# mix1_LO1.net
KiCad netlist of a schematic drawn in Altium Designer
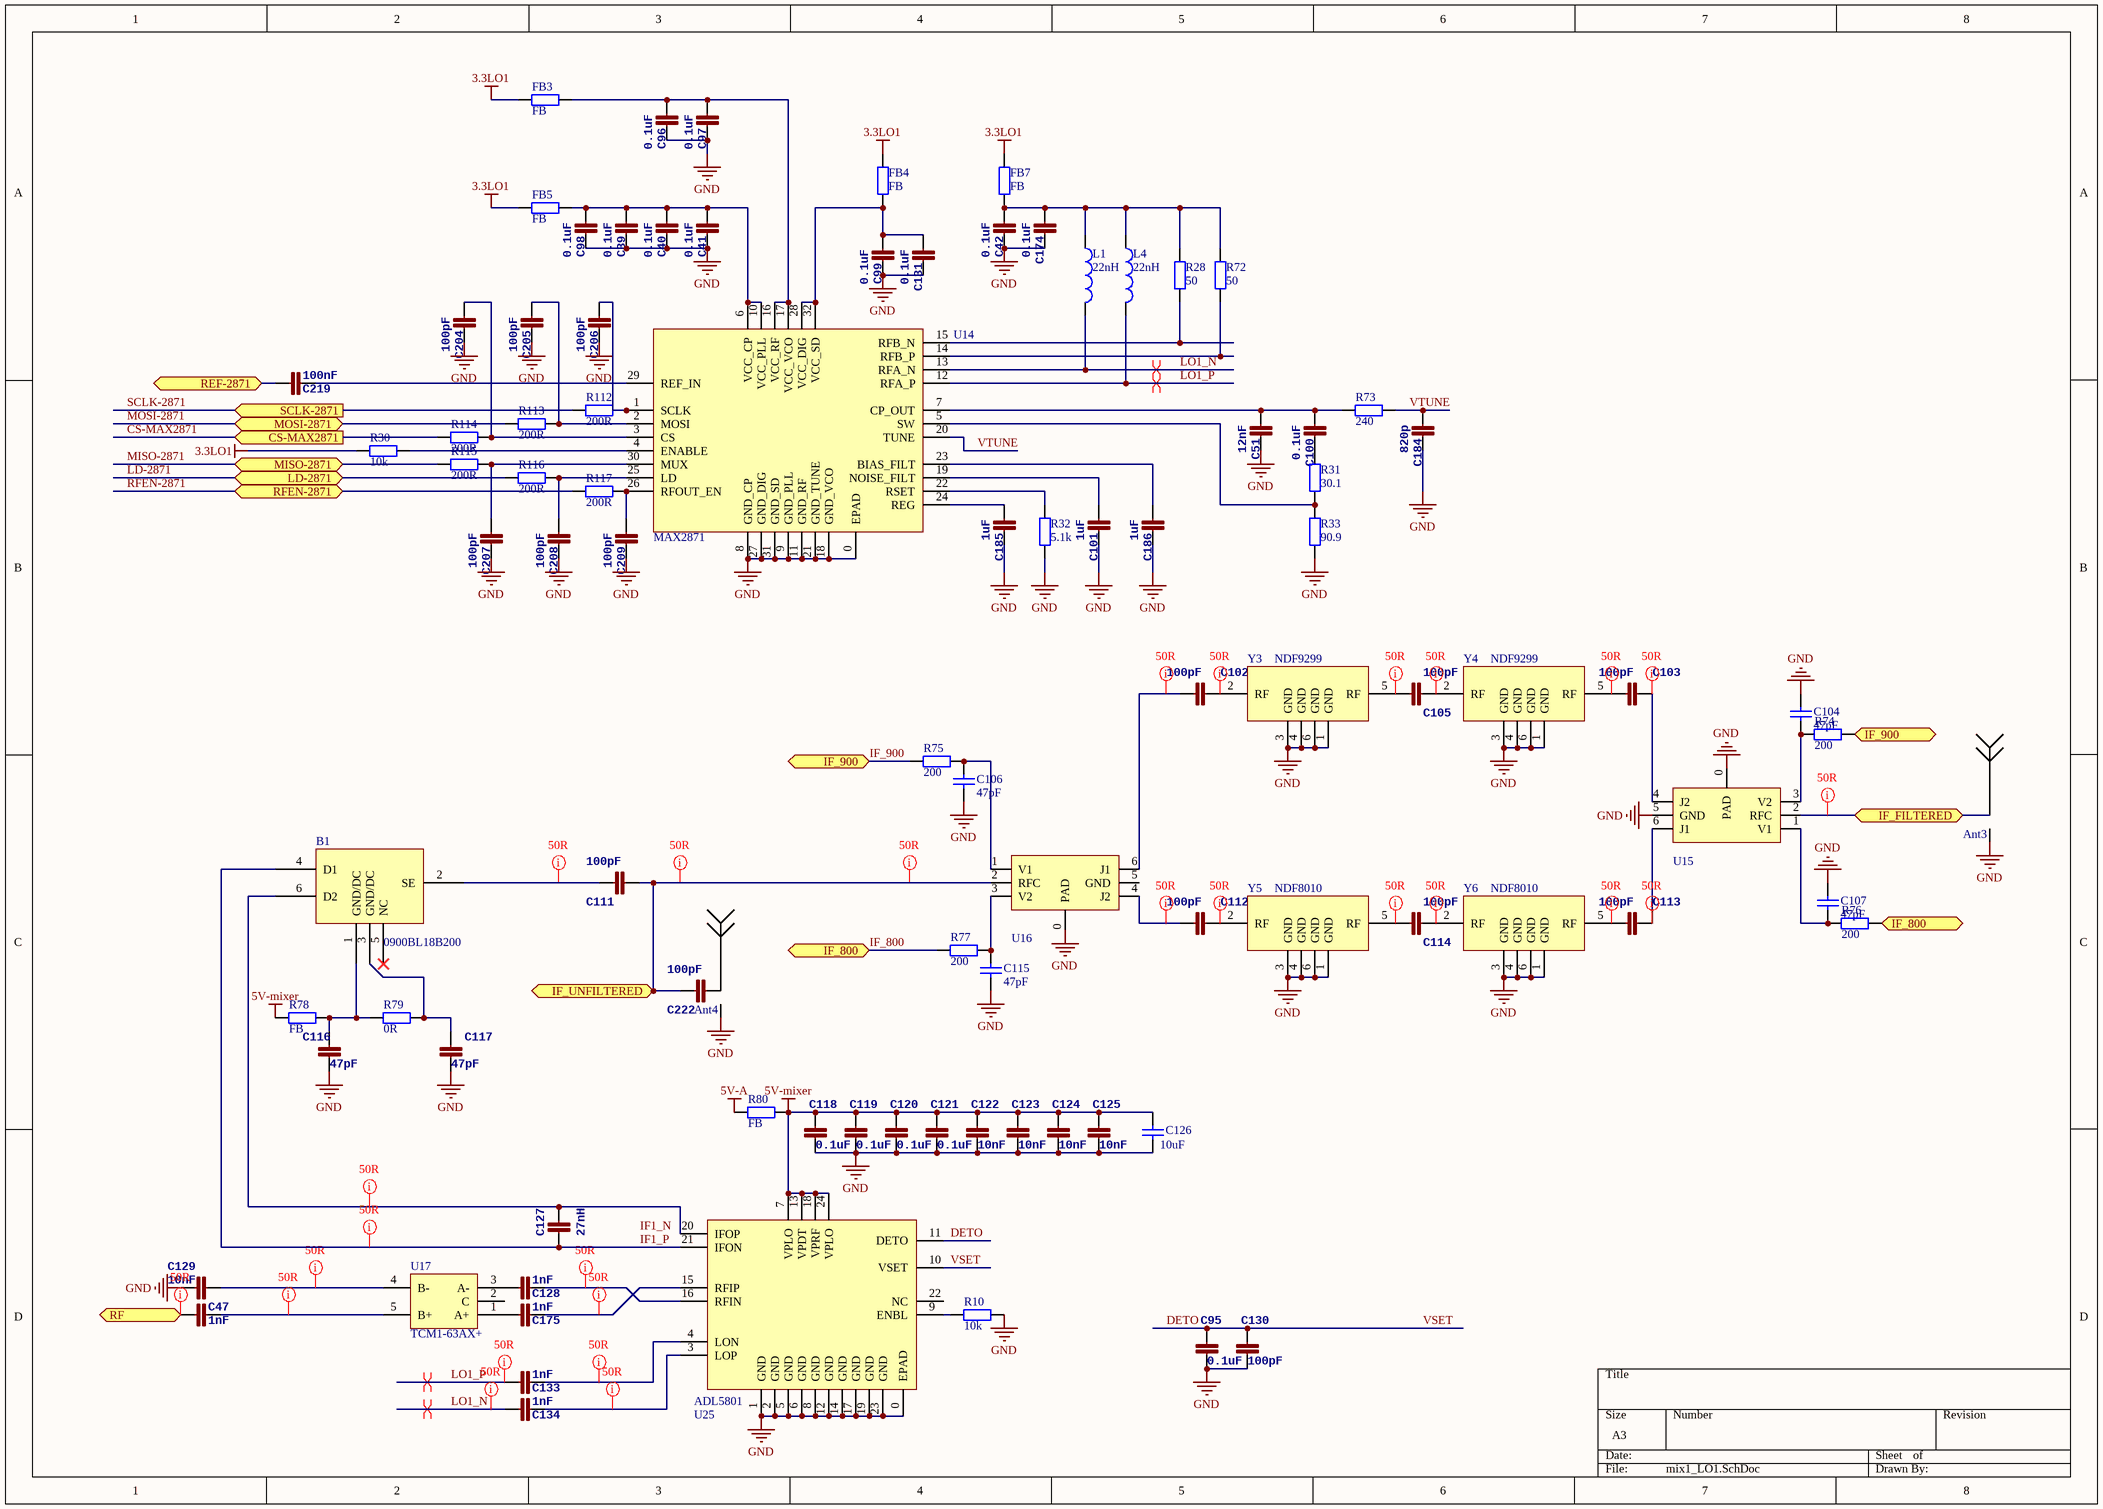
[diagram p0: mix1_LO1.SchDoc]

(export (version "E")
  (design (tool "Eeschema 10.0.6"))
  (components
    (comp (ref "Ant3") (value "Antenna") (footprint "SMA-SMT") (libsource (lib "F4SDR") (part "Antenna")))
    (comp (ref "Ant4") (value "Antenna") (footprint "SMA-SMT") (libsource (lib "F4SDR") (part "Antenna")))
    (comp (ref "B1")
      (value "0900BL18B200")
      (footprint "0900BL18B200")
      (libsource (lib "F4SDR") (part "0900BL18B200"))
    )
    (comp (ref "C39")
      (value "0.1uF")
      (footprint "0402")
      (description "<b>Capacitor</b>\nStandard 0603 ceramic capacitor, and 0.1\" leaded capacitor.")
      (fields (field (name "PARTNO") "CC0402ZRY5V7BB104"))
      (libsource (lib "pixhawk2") (part "CAP0402-CAP"))
    )
    (comp (ref "C40")
      (value "0.1uF")
      (footprint "0402")
      (description "<b>Capacitor</b>\nStandard 0603 ceramic capacitor, and 0.1\" leaded capacitor.")
      (fields (field (name "PARTNO") "CC0402ZRY5V7BB104"))
      (libsource (lib "pixhawk2") (part "CAP0402-CAP"))
    )
    (comp (ref "C41")
      (value "0.1uF")
      (footprint "0402")
      (description "<b>Capacitor</b>\nStandard 0603 ceramic capacitor, and 0.1\" leaded capacitor.")
      (fields (field (name "PARTNO") "CC0402ZRY5V7BB104"))
      (libsource (lib "pixhawk2") (part "CAP0402-CAP"))
    )
    (comp (ref "C42")
      (value "0.1uF")
      (footprint "0402")
      (description "<b>Capacitor</b>\nStandard 0603 ceramic capacitor, and 0.1\" leaded capacitor.")
      (fields (field (name "PARTNO") "CC0402ZRY5V7BB104"))
      (libsource (lib "pixhawk2") (part "CAP0402-CAP"))
    )
    (comp (ref "C47")
      (value "1nF")
      (footprint "0402")
      (description "<b>Capacitor</b>\nStandard 0603 ceramic capacitor, and 0.1\" leaded capacitor.")
      (fields (field (name "PARTNO") "CC0402ZRY5V7BB104"))
      (libsource (lib "*") (part "CAP0402-CAP"))
    )
    (comp (ref "C51")
      (value "12nF")
      (footprint "0402")
      (description "<b>Capacitor</b>\nStandard 0603 ceramic capacitor, and 0.1\" leaded capacitor.")
      (fields (field (name "PARTNO") "CC0402ZRY5V7BB104"))
      (libsource (lib "pixhawk2") (part "CAP0402-CAP"))
    )
    (comp (ref "C95")
      (value "0.1uF")
      (footprint "0402")
      (description "<b>Capacitor</b>\nStandard 0603 ceramic capacitor, and 0.1\" leaded capacitor.")
      (fields (field (name "PARTNO") "CC0402ZRY5V7BB104"))
      (libsource (lib "") (part "CAP0402-CAP_1"))
    )
    (comp (ref "C96")
      (value "0.1uF")
      (footprint "0402")
      (description "<b>Capacitor</b>\nStandard 0603 ceramic capacitor, and 0.1\" leaded capacitor.")
      (fields (field (name "PARTNO") "CC0402ZRY5V7BB104"))
      (libsource (lib "pixhawk2") (part "CAP0402-CAP"))
    )
    (comp (ref "C97")
      (value "0.1uF")
      (footprint "0402")
      (description "<b>Capacitor</b>\nStandard 0603 ceramic capacitor, and 0.1\" leaded capacitor.")
      (fields (field (name "PARTNO") "CC0402ZRY5V7BB104"))
      (libsource (lib "pixhawk2") (part "CAP0402-CAP"))
    )
    (comp (ref "C98")
      (value "0.1uF")
      (footprint "0402")
      (description "<b>Capacitor</b>\nStandard 0603 ceramic capacitor, and 0.1\" leaded capacitor.")
      (fields (field (name "PARTNO") "CC0402ZRY5V7BB104"))
      (libsource (lib "pixhawk2") (part "CAP0402-CAP"))
    )
    (comp (ref "C99")
      (value "0.1uF")
      (footprint "0402")
      (description "<b>Capacitor</b>\nStandard 0603 ceramic capacitor, and 0.1\" leaded capacitor.")
      (fields (field (name "PARTNO") "CC0402ZRY5V7BB104"))
      (libsource (lib "pixhawk2") (part "CAP0402-CAP"))
    )
    (comp (ref "C100")
      (value "0.1uF")
      (footprint "0402")
      (description "<b>Capacitor</b>\nStandard 0603 ceramic capacitor, and 0.1\" leaded capacitor.")
      (fields (field (name "PARTNO") "CC0402ZRY5V7BB104"))
      (libsource (lib "pixhawk2") (part "CAP0402-CAP"))
    )
    (comp (ref "C101")
      (value "1uF")
      (footprint "0402")
      (description "<b>Capacitor</b>\nStandard 0603 ceramic capacitor, and 0.1\" leaded capacitor.")
      (fields (field (name "PARTNO") "CC0402ZRY5V7BB104"))
      (libsource (lib "pixhawk2") (part "CAP0402-CAP"))
    )
    (comp (ref "C102")
      (value "100pF")
      (footprint "0402")
      (description "<b>Capacitor</b>\nStandard 0603 ceramic capacitor, and 0.1\" leaded capacitor.")
      (fields (field (name "PARTNO") "CC0402ZRY5V7BB104"))
      (libsource (lib "") (part "CAP0402-CAP_2"))
    )
    (comp (ref "C103")
      (value "100pF")
      (footprint "0402")
      (description "<b>Capacitor</b>\nStandard 0603 ceramic capacitor, and 0.1\" leaded capacitor.")
      (fields (field (name "PARTNO") "CC0402ZRY5V7BB104"))
      (libsource (lib "") (part "CAP0402-CAP_2"))
    )
    (comp (ref "C104")
      (value "47pF")
      (footprint "0402")
      (description "Capacitor")
      (fields (field (name "PUBLISHER") "Altium Limited"))
      (libsource (lib "RTC6705") (part "Cap"))
    )
    (comp (ref "C105")
      (value "100pF")
      (footprint "0402")
      (description "<b>Capacitor</b>\nStandard 0603 ceramic capacitor, and 0.1\" leaded capacitor.")
      (fields (field (name "PARTNO") "CC0402ZRY5V7BB104"))
      (libsource (lib "") (part "CAP0402-CAP_2"))
    )
    (comp (ref "C106")
      (value "47pF")
      (footprint "0402")
      (description "Capacitor")
      (fields (field (name "PUBLISHER") "Altium Limited"))
      (libsource (lib "RTC6705") (part "Cap"))
    )
    (comp (ref "C107")
      (value "47pF")
      (footprint "0402")
      (description "Capacitor")
      (fields (field (name "PUBLISHER") "Altium Limited"))
      (libsource (lib "RTC6705") (part "Cap"))
    )
    (comp (ref "C111")
      (value "100pF")
      (footprint "0402")
      (description "<b>Capacitor</b>\nStandard 0603 ceramic capacitor, and 0.1\" leaded capacitor.")
      (fields (field (name "PARTNO") "CC0402ZRY5V7BB104"))
      (libsource (lib "") (part "CAP0402-CAP_2"))
    )
    (comp (ref "C112")
      (value "100pF")
      (footprint "0402")
      (description "<b>Capacitor</b>\nStandard 0603 ceramic capacitor, and 0.1\" leaded capacitor.")
      (fields (field (name "PARTNO") "CC0402ZRY5V7BB104"))
      (libsource (lib "") (part "CAP0402-CAP_2"))
    )
    (comp (ref "C113")
      (value "100pF")
      (footprint "0402")
      (description "<b>Capacitor</b>\nStandard 0603 ceramic capacitor, and 0.1\" leaded capacitor.")
      (fields (field (name "PARTNO") "CC0402ZRY5V7BB104"))
      (libsource (lib "") (part "CAP0402-CAP_2"))
    )
    (comp (ref "C114")
      (value "100pF")
      (footprint "0402")
      (description "<b>Capacitor</b>\nStandard 0603 ceramic capacitor, and 0.1\" leaded capacitor.")
      (fields (field (name "PARTNO") "CC0402ZRY5V7BB104"))
      (libsource (lib "") (part "CAP0402-CAP_2"))
    )
    (comp (ref "C115")
      (value "47pF")
      (footprint "0402")
      (description "Capacitor")
      (fields (field (name "PUBLISHER") "Altium Limited"))
      (libsource (lib "RTC6705") (part "Cap"))
    )
    (comp (ref "C116")
      (value "47pF")
      (footprint "0402")
      (description "<b>Capacitor</b>\nStandard 0603 ceramic capacitor, and 0.1\" leaded capacitor.")
      (fields (field (name "PARTNO") "CC0402ZRY5V7BB104"))
      (libsource (lib "") (part "CAP0402-CAP_1"))
    )
    (comp (ref "C117")
      (value "47pF")
      (footprint "0402")
      (description "<b>Capacitor</b>\nStandard 0603 ceramic capacitor, and 0.1\" leaded capacitor.")
      (fields (field (name "PARTNO") "CC0402ZRY5V7BB104"))
      (libsource (lib "") (part "CAP0402-CAP_1"))
    )
    (comp (ref "C118")
      (value "0.1uF")
      (footprint "0402")
      (description "<b>Capacitor</b>\nStandard 0603 ceramic capacitor, and 0.1\" leaded capacitor.")
      (fields (field (name "PARTNO") "CC0402ZRY5V7BB104"))
      (libsource (lib "") (part "CAP0402-CAP_1"))
    )
    (comp (ref "C119")
      (value "0.1uF")
      (footprint "0402")
      (description "<b>Capacitor</b>\nStandard 0603 ceramic capacitor, and 0.1\" leaded capacitor.")
      (fields (field (name "PARTNO") "CC0402ZRY5V7BB104"))
      (libsource (lib "") (part "CAP0402-CAP_1"))
    )
    (comp (ref "C120")
      (value "0.1uF")
      (footprint "0402")
      (description "<b>Capacitor</b>\nStandard 0603 ceramic capacitor, and 0.1\" leaded capacitor.")
      (fields (field (name "PARTNO") "CC0402ZRY5V7BB104"))
      (libsource (lib "") (part "CAP0402-CAP_1"))
    )
    (comp (ref "C121")
      (value "0.1uF")
      (footprint "0402")
      (description "<b>Capacitor</b>\nStandard 0603 ceramic capacitor, and 0.1\" leaded capacitor.")
      (fields (field (name "PARTNO") "CC0402ZRY5V7BB104"))
      (libsource (lib "") (part "CAP0402-CAP_1"))
    )
    (comp (ref "C122")
      (value "10nF")
      (footprint "0402")
      (description "<b>Capacitor</b>\nStandard 0603 ceramic capacitor, and 0.1\" leaded capacitor.")
      (fields (field (name "PARTNO") "CC0402ZRY5V7BB104"))
      (libsource (lib "") (part "CAP0402-CAP_1"))
    )
    (comp (ref "C123")
      (value "10nF")
      (footprint "0402")
      (description "<b>Capacitor</b>\nStandard 0603 ceramic capacitor, and 0.1\" leaded capacitor.")
      (fields (field (name "PARTNO") "CC0402ZRY5V7BB104"))
      (libsource (lib "") (part "CAP0402-CAP_1"))
    )
    (comp (ref "C124")
      (value "10nF")
      (footprint "0402")
      (description "<b>Capacitor</b>\nStandard 0603 ceramic capacitor, and 0.1\" leaded capacitor.")
      (fields (field (name "PARTNO") "CC0402ZRY5V7BB104"))
      (libsource (lib "") (part "CAP0402-CAP_1"))
    )
    (comp (ref "C125")
      (value "10nF")
      (footprint "0402")
      (description "<b>Capacitor</b>\nStandard 0603 ceramic capacitor, and 0.1\" leaded capacitor.")
      (fields (field (name "PARTNO") "CC0402ZRY5V7BB104"))
      (libsource (lib "") (part "CAP0402-CAP_1"))
    )
    (comp (ref "C126")
      (value "10uF")
      (footprint "0805")
      (description "Capacitor")
      (fields (field (name "PUBLISHER") "Altium Limited"))
      (libsource (lib "RTC6705") (part "Cap"))
    )
    (comp (ref "C127")
      (value "27nH")
      (footprint "0402")
      (description "<b>Capacitor</b>\nStandard 0603 ceramic capacitor, and 0.1\" leaded capacitor.")
      (fields (field (name "PARTNO") "CC0402ZRY5V7BB104"))
      (libsource (lib "") (part "CAP0402-CAP_3"))
    )
    (comp (ref "C128")
      (value "1nF")
      (footprint "0402")
      (description "<b>Capacitor</b>\nStandard 0603 ceramic capacitor, and 0.1\" leaded capacitor.")
      (fields (field (name "PARTNO") "CC0402ZRY5V7BB104"))
      (libsource (lib "*") (part "CAP0402-CAP"))
    )
    (comp (ref "C129")
      (value "10nF")
      (footprint "0402")
      (description "<b>Capacitor</b>\nStandard 0603 ceramic capacitor, and 0.1\" leaded capacitor.")
      (fields (field (name "PARTNO") "CC0402ZRY5V7BB104"))
      (libsource (lib "") (part "CAP0402-CAP_2"))
    )
    (comp (ref "C130")
      (value "100pF")
      (footprint "0402")
      (description "<b>Capacitor</b>\nStandard 0603 ceramic capacitor, and 0.1\" leaded capacitor.")
      (fields (field (name "PARTNO") "CC0402ZRY5V7BB104"))
      (libsource (lib "") (part "CAP0402-CAP_1"))
    )
    (comp (ref "C131")
      (value "0.1uF")
      (footprint "0402")
      (description "<b>Capacitor</b>\nStandard 0603 ceramic capacitor, and 0.1\" leaded capacitor.")
      (fields (field (name "PARTNO") "CC0402ZRY5V7BB104"))
      (libsource (lib "pixhawk2") (part "CAP0402-CAP"))
    )
    (comp (ref "C133")
      (value "1nF")
      (footprint "0402")
      (description "<b>Capacitor</b>\nStandard 0603 ceramic capacitor, and 0.1\" leaded capacitor.")
      (fields (field (name "PARTNO") "CC0402ZRY5V7BB104"))
      (libsource (lib "*") (part "CAP0402-CAP"))
    )
    (comp (ref "C134")
      (value "1nF")
      (footprint "0402")
      (description "<b>Capacitor</b>\nStandard 0603 ceramic capacitor, and 0.1\" leaded capacitor.")
      (fields (field (name "PARTNO") "CC0402ZRY5V7BB104"))
      (libsource (lib "*") (part "CAP0402-CAP"))
    )
    (comp (ref "C174")
      (value "0.1uF")
      (footprint "0402")
      (description "<b>Capacitor</b>\nStandard 0603 ceramic capacitor, and 0.1\" leaded capacitor.")
      (fields (field (name "PARTNO") "CC0402ZRY5V7BB104"))
      (libsource (lib "pixhawk2") (part "CAP0402-CAP"))
    )
    (comp (ref "C175")
      (value "1nF")
      (footprint "0402")
      (description "<b>Capacitor</b>\nStandard 0603 ceramic capacitor, and 0.1\" leaded capacitor.")
      (fields (field (name "PARTNO") "CC0402ZRY5V7BB104"))
      (libsource (lib "*") (part "CAP0402-CAP"))
    )
    (comp (ref "C184")
      (value "820p")
      (footprint "0402")
      (description "<b>Capacitor</b>\nStandard 0603 ceramic capacitor, and 0.1\" leaded capacitor.")
      (fields (field (name "PARTNO") "CC0402ZRY5V7BB104"))
      (libsource (lib "pixhawk2") (part "CAP0402-CAP"))
    )
    (comp (ref "C185")
      (value "1uF")
      (footprint "0402")
      (description "<b>Capacitor</b>\nStandard 0603 ceramic capacitor, and 0.1\" leaded capacitor.")
      (fields (field (name "PARTNO") "CC0402ZRY5V7BB104"))
      (libsource (lib "pixhawk2") (part "CAP0402-CAP"))
    )
    (comp (ref "C186")
      (value "1uF")
      (footprint "0402")
      (description "<b>Capacitor</b>\nStandard 0603 ceramic capacitor, and 0.1\" leaded capacitor.")
      (fields (field (name "PARTNO") "CC0402ZRY5V7BB104"))
      (libsource (lib "pixhawk2") (part "CAP0402-CAP"))
    )
    (comp (ref "C204")
      (value "100pF")
      (footprint "0402")
      (description "<b>Capacitor</b>\nStandard 0603 ceramic capacitor, and 0.1\" leaded capacitor.")
      (fields (field (name "PARTNO") "CC0402ZRY5V7BB104"))
      (libsource (lib "pixhawk2") (part "CAP0402-CAP"))
    )
    (comp (ref "C205")
      (value "100pF")
      (footprint "0402")
      (description "<b>Capacitor</b>\nStandard 0603 ceramic capacitor, and 0.1\" leaded capacitor.")
      (fields (field (name "PARTNO") "CC0402ZRY5V7BB104"))
      (libsource (lib "pixhawk2") (part "CAP0402-CAP"))
    )
    (comp (ref "C206")
      (value "100pF")
      (footprint "0402")
      (description "<b>Capacitor</b>\nStandard 0603 ceramic capacitor, and 0.1\" leaded capacitor.")
      (fields (field (name "PARTNO") "CC0402ZRY5V7BB104"))
      (libsource (lib "pixhawk2") (part "CAP0402-CAP"))
    )
    (comp (ref "C207")
      (value "100pF")
      (footprint "0402")
      (description "<b>Capacitor</b>\nStandard 0603 ceramic capacitor, and 0.1\" leaded capacitor.")
      (fields (field (name "PARTNO") "CC0402ZRY5V7BB104"))
      (libsource (lib "pixhawk2") (part "CAP0402-CAP"))
    )
    (comp (ref "C208")
      (value "100pF")
      (footprint "0402")
      (description "<b>Capacitor</b>\nStandard 0603 ceramic capacitor, and 0.1\" leaded capacitor.")
      (fields (field (name "PARTNO") "CC0402ZRY5V7BB104"))
      (libsource (lib "pixhawk2") (part "CAP0402-CAP"))
    )
    (comp (ref "C209")
      (value "100pF")
      (footprint "0402")
      (description "<b>Capacitor</b>\nStandard 0603 ceramic capacitor, and 0.1\" leaded capacitor.")
      (fields (field (name "PARTNO") "CC0402ZRY5V7BB104"))
      (libsource (lib "pixhawk2") (part "CAP0402-CAP"))
    )
    (comp (ref "C219")
      (value "100nF")
      (footprint "0402")
      (description "<b>Capacitor</b>\nStandard 0603 ceramic capacitor, and 0.1\" leaded capacitor.")
      (fields (field (name "PARTNO") "CC0402ZRY5V7BB104"))
      (libsource (lib "") (part "CAP0402-CAP_1"))
    )
    (comp (ref "C222")
      (value "100pF")
      (footprint "0402")
      (description "<b>Capacitor</b>\nStandard 0603 ceramic capacitor, and 0.1\" leaded capacitor.")
      (fields (field (name "PARTNO") "CC0402ZRY5V7BB104"))
      (libsource (lib "") (part "CAP0402-CAP_2"))
    )
    (comp (ref "FB3")
      (value "FB")
      (footprint "0603")
      (description "Resistor")
      (fields (field (name "PUBLISHER") "Altium Limited"))
      (libsource (lib "") (part "Res2_1"))
    )
    (comp (ref "FB4")
      (value "FB")
      (footprint "0603")
      (description "Resistor")
      (fields (field (name "PUBLISHER") "Altium Limited"))
      (libsource (lib "") (part "Res2_3"))
    )
    (comp (ref "FB5")
      (value "FB")
      (footprint "0603")
      (description "Resistor")
      (fields (field (name "PUBLISHER") "Altium Limited"))
      (libsource (lib "") (part "Res2_1"))
    )
    (comp (ref "FB7")
      (value "FB")
      (footprint "0603")
      (description "Resistor")
      (fields (field (name "PUBLISHER") "Altium Limited"))
      (libsource (lib "") (part "Res2_3"))
    )
    (comp (ref "L1")
      (value "22nH")
      (footprint "0402")
      (description "Inductor")
      (fields (field (name "PUBLISHER") "Altium Limited"))
      (libsource (lib "Miscellaneous Devices") (part "Inductor"))
    )
    (comp (ref "L4")
      (value "22nH")
      (footprint "0402")
      (description "Inductor")
      (fields (field (name "PUBLISHER") "Altium Limited"))
      (libsource (lib "Miscellaneous Devices") (part "Inductor"))
    )
    (comp (ref "R10")
      (value "10k")
      (footprint "0402")
      (description "Resistor")
      (fields (field (name "Comment") "Res2") (field (name "PUBLISHER") "Altium Limited"))
      (libsource (lib "") (part "Res2_1"))
    )
    (comp (ref "R28")
      (value "50")
      (footprint "0402")
      (description "Resistor")
      (fields (field (name "PUBLISHER") "Altium Limited"))
      (libsource (lib "") (part "Res2_3"))
    )
    (comp (ref "R30")
      (value "10k")
      (footprint "0402")
      (description "Resistor")
      (fields (field (name "PUBLISHER") "Altium Limited"))
      (libsource (lib "") (part "Res2_1"))
    )
    (comp (ref "R31")
      (value "30.1")
      (footprint "0402")
      (description "Resistor")
      (fields (field (name "PUBLISHER") "Altium Limited"))
      (libsource (lib "Miscellaneous Devices") (part "Res2"))
    )
    (comp (ref "R32")
      (value "5.1k")
      (footprint "0402")
      (description "Resistor")
      (fields (field (name "PUBLISHER") "Altium Limited"))
      (libsource (lib "Miscellaneous Devices") (part "Res2"))
    )
    (comp (ref "R33")
      (value "90.9")
      (footprint "0402")
      (description "Resistor")
      (fields (field (name "PUBLISHER") "Altium Limited"))
      (libsource (lib "Miscellaneous Devices") (part "Res2"))
    )
    (comp (ref "R72")
      (value "50")
      (footprint "0402")
      (description "Resistor")
      (fields (field (name "PUBLISHER") "Altium Limited"))
      (libsource (lib "") (part "Res2_3"))
    )
    (comp (ref "R73")
      (value "240")
      (footprint "0402")
      (description "Resistor")
      (fields (field (name "PUBLISHER") "Altium Limited"))
      (libsource (lib "") (part "Res2_1"))
    )
    (comp (ref "R74")
      (value "200")
      (footprint "0402")
      (description "Resistor")
      (fields (field (name "PUBLISHER") "Altium Limited"))
      (libsource (lib "RTC6705") (part "Res2"))
    )
    (comp (ref "R75")
      (value "200")
      (footprint "0402")
      (description "Resistor")
      (fields (field (name "PUBLISHER") "Altium Limited"))
      (libsource (lib "") (part "Res2_1"))
    )
    (comp (ref "R76")
      (value "200")
      (footprint "0402")
      (description "Resistor")
      (fields (field (name "PUBLISHER") "Altium Limited"))
      (libsource (lib "RTC6705") (part "Res2"))
    )
    (comp (ref "R77")
      (value "200")
      (footprint "0402")
      (description "Resistor")
      (fields (field (name "PUBLISHER") "Altium Limited"))
      (libsource (lib "") (part "Res2_1"))
    )
    (comp (ref "R78")
      (value "FB")
      (footprint "0402")
      (description "Resistor")
      (fields (field (name "PUBLISHER") "Altium Limited"))
      (libsource (lib "") (part "Res2_2"))
    )
    (comp (ref "R79")
      (value "0R")
      (footprint "0402")
      (description "Resistor")
      (fields (field (name "PUBLISHER") "Altium Limited"))
      (libsource (lib "") (part "Res2_2"))
    )
    (comp (ref "R80")
      (value "FB")
      (footprint "0603")
      (description "Resistor")
      (fields (field (name "PUBLISHER") "Altium Limited"))
      (libsource (lib "") (part "Res2_2"))
    )
    (comp (ref "R112")
      (value "200R")
      (footprint "0402")
      (description "Resistor")
      (fields (field (name "PUBLISHER") "Altium Limited"))
      (libsource (lib "") (part "Res2_1"))
    )
    (comp (ref "R113")
      (value "200R")
      (footprint "0402")
      (description "Resistor")
      (fields (field (name "PUBLISHER") "Altium Limited"))
      (libsource (lib "") (part "Res2_1"))
    )
    (comp (ref "R114")
      (value "200R")
      (footprint "0402")
      (description "Resistor")
      (fields (field (name "PUBLISHER") "Altium Limited"))
      (libsource (lib "") (part "Res2_1"))
    )
    (comp (ref "R115")
      (value "200R")
      (footprint "0402")
      (description "Resistor")
      (fields (field (name "PUBLISHER") "Altium Limited"))
      (libsource (lib "") (part "Res2_1"))
    )
    (comp (ref "R116")
      (value "200R")
      (footprint "0402")
      (description "Resistor")
      (fields (field (name "PUBLISHER") "Altium Limited"))
      (libsource (lib "") (part "Res2_1"))
    )
    (comp (ref "R117")
      (value "200R")
      (footprint "0402")
      (description "Resistor")
      (fields (field (name "PUBLISHER") "Altium Limited"))
      (libsource (lib "") (part "Res2_1"))
    )
    (comp (ref "U14") (value "MAX2871") (footprint "MAX2871") (libsource (lib "F4SDR") (part "MAX2871")))
    (comp (ref "U15")
      (value "SKY13320")
      (footprint "SKY65404-31")
      (libsource (lib "F4SDR") (part "SKY13320"))
    )
    (comp (ref "U16") (value "SKY13320") (footprint "SKY65404-31") (libsource (lib "") (part "SKY13320_1")))
    (comp (ref "U17")
      (value "TCM1-63AX+")
      (footprint "TCM-63AX+")
      (libsource (lib "F4SDR") (part "TCM1-1-13M+"))
    )
    (comp (ref "U25") (value "ADL5801") (footprint "ADL5801") (libsource (lib "F4SDR") (part "ADL5801")))
    (comp (ref "Y3") (value "NDF9299") (footprint "NDF8010") (libsource (lib "F4SDR") (part "NDF8010")))
    (comp (ref "Y4") (value "NDF9299") (footprint "NDF8010") (libsource (lib "F4SDR") (part "NDF8010")))
    (comp (ref "Y5") (value "NDF8010") (footprint "NDF8010") (libsource (lib "F4SDR") (part "NDF8010")))
    (comp (ref "Y6") (value "NDF8010") (footprint "NDF8010") (libsource (lib "F4SDR") (part "NDF8010")))
  )
  (nets
    (net (code "1") (name "/CS-MAX2871") (class "Default")
      (node (ref "R114") (pin "2") (pinfunction "2_2") (pintype "passive"))
    )
    (net (code "2") (name "/DETO") (class "Default")
      (node (ref "C130") (pin "2") (pinfunction "2_2") (pintype "passive"))
      (node (ref "C95") (pin "2") (pinfunction "2_2") (pintype "passive"))
      (node (ref "U25") (pin "10") (pinfunction "VSET_10") (pintype "passive"))
      (node (ref "U25") (pin "11") (pinfunction "DETO_11") (pintype "passive"))
    )
    (net (code "4") (name "/IF1_P") (class "Default")
      (node (ref "B1") (pin "4") (pinfunction "D1_4") (pintype "passive"))
      (node (ref "C127") (pin "2") (pinfunction "2_2") (pintype "passive"))
      (node (ref "U25") (pin "21") (pinfunction "IFON_21") (pintype "passive"))
    )
    (net (code "5") (name "/IF_800") (class "Default")
      (node (ref "R76") (pin "1") (pinfunction "1_1") (pintype "passive"))
      (node (ref "R77") (pin "1") (pinfunction "1_1") (pintype "passive"))
    )
    (net (code "6") (name "/IF_900") (class "Default")
      (node (ref "R74") (pin "1") (pinfunction "1_1") (pintype "passive"))
      (node (ref "R75") (pin "1") (pinfunction "1_1") (pintype "passive"))
    )
    (net (code "7") (name "/IF_FILTERED") (class "Default")
      (node (ref "Ant3") (pin "1") (pinfunction "1_1") (pintype "passive"))
      (node (ref "U15") (pin "2") (pinfunction "RFC_2") (pintype "passive"))
    )
    (net (code "8") (name "/IF_UNFILTERED") (class "Default")
      (node (ref "C111") (pin "1") (pinfunction "1_1") (pintype "passive"))
      (node (ref "C222") (pin "2") (pinfunction "2_2") (pintype "passive"))
      (node (ref "U16") (pin "2") (pinfunction "RFC_2") (pintype "passive"))
    )
    (net (code "9") (name "/LD-2871") (class "Default")
      (node (ref "R116") (pin "2") (pinfunction "2_2") (pintype "passive"))
    )
    (net (code "10") (name "/LO1_N") (class "Default")
      (node (ref "C134") (pin "1") (pinfunction "1_1") (pintype "passive"))
      (node (ref "L1") (pin "2") (pinfunction "2_2") (pintype "passive"))
      (node (ref "U14") (pin "13") (pinfunction "RFA_N_13") (pintype "passive"))
    )
    (net (code "11") (name "/LO1_P") (class "Default")
      (node (ref "C133") (pin "1") (pinfunction "1_1") (pintype "passive"))
      (node (ref "L4") (pin "2") (pinfunction "2_2") (pintype "passive"))
      (node (ref "U14") (pin "12") (pinfunction "RFA_P_12") (pintype "passive"))
    )
    (net (code "12") (name "/MISO-2871") (class "Default")
      (node (ref "R115") (pin "2") (pinfunction "2_2") (pintype "passive"))
    )
    (net (code "13") (name "/MOSI-2871") (class "Default")
      (node (ref "R113") (pin "2") (pinfunction "2_2") (pintype "passive"))
    )
    (net (code "14") (name "/REF-2871") (class "Default")
      (node (ref "C219") (pin "1") (pinfunction "1_1") (pintype "passive"))
    )
    (net (code "15") (name "/RF") (class "Default")
      (node (ref "C129") (pin "2") (pinfunction "2_2") (pintype "passive"))
    )
    (net (code "16") (name "/RFEN-2871") (class "Default")
      (node (ref "R117") (pin "2") (pinfunction "2_2") (pintype "passive"))
    )
    (net (code "17") (name "/SCLK-2871") (class "Default")
      (node (ref "R112") (pin "2") (pinfunction "2_2") (pintype "passive"))
    )
    (net (code "18") (name "/VTUNE") (class "Default")
      (node (ref "C184") (pin "1") (pinfunction "1_1") (pintype "passive"))
      (node (ref "R73") (pin "1") (pinfunction "1_1") (pintype "passive"))
      (node (ref "U14") (pin "20") (pinfunction "TUNE_20") (pintype "passive"))
    )
    (net (code "19") (name "3.3LO1") (class "Default")
      (node (ref "FB3") (pin "2") (pinfunction "2_2") (pintype "passive"))
      (node (ref "FB4") (pin "1") (pinfunction "1_1") (pintype "passive"))
      (node (ref "FB5") (pin "2") (pinfunction "2_2") (pintype "passive"))
      (node (ref "FB7") (pin "1") (pinfunction "1_1") (pintype "passive"))
      (node (ref "R30") (pin "2") (pinfunction "2_2") (pintype "passive"))
    )
    (net (code "20") (name "5V-A") (class "Default")
      (node (ref "R80") (pin "1") (pinfunction "1_1") (pintype "passive"))
    )
    (net (code "21") (name "5V-mixer") (class "Default")
      (node (ref "C118") (pin "2") (pinfunction "2_2") (pintype "passive"))
      (node (ref "C119") (pin "2") (pinfunction "2_2") (pintype "passive"))
      (node (ref "C120") (pin "2") (pinfunction "2_2") (pintype "passive"))
      (node (ref "C121") (pin "2") (pinfunction "2_2") (pintype "passive"))
      (node (ref "C122") (pin "2") (pinfunction "2_2") (pintype "passive"))
      (node (ref "C123") (pin "2") (pinfunction "2_2") (pintype "passive"))
      (node (ref "C124") (pin "2") (pinfunction "2_2") (pintype "passive"))
      (node (ref "C125") (pin "2") (pinfunction "2_2") (pintype "passive"))
      (node (ref "C126") (pin "2") (pinfunction "2_2") (pintype "passive"))
      (node (ref "R78") (pin "1") (pinfunction "1_1") (pintype "passive"))
      (node (ref "R80") (pin "2") (pinfunction "2_2") (pintype "passive"))
      (node (ref "U25") (pin "13") (pinfunction "VPDT_13") (pintype "passive"))
      (node (ref "U25") (pin "18") (pinfunction "VPRF_18") (pintype "passive"))
      (node (ref "U25") (pin "24") (pinfunction "VPLO_24") (pintype "passive"))
      (node (ref "U25") (pin "7") (pinfunction "VPLO_7") (pintype "passive"))
    )
    (net (code "22") (name "GND") (class "Default")
      (node (ref "Ant3") (pin "GND") (pinfunction "G_GND") (pintype "passive"))
      (node (ref "Ant4") (pin "GND") (pinfunction "G_GND") (pintype "passive"))
      (node (ref "C101") (pin "2") (pinfunction "2_2") (pintype "passive"))
      (node (ref "C104") (pin "1") (pinfunction "1_1") (pintype "passive"))
      (node (ref "C106") (pin "1") (pinfunction "1_1") (pintype "passive"))
      (node (ref "C107") (pin "1") (pinfunction "1_1") (pintype "passive"))
      (node (ref "C115") (pin "1") (pinfunction "1_1") (pintype "passive"))
      (node (ref "C116") (pin "1") (pinfunction "1_1") (pintype "passive"))
      (node (ref "C117") (pin "1") (pinfunction "1_1") (pintype "passive"))
      (node (ref "C118") (pin "1") (pinfunction "1_1") (pintype "passive"))
      (node (ref "C119") (pin "1") (pinfunction "1_1") (pintype "passive"))
      (node (ref "C120") (pin "1") (pinfunction "1_1") (pintype "passive"))
      (node (ref "C121") (pin "1") (pinfunction "1_1") (pintype "passive"))
      (node (ref "C122") (pin "1") (pinfunction "1_1") (pintype "passive"))
      (node (ref "C123") (pin "1") (pinfunction "1_1") (pintype "passive"))
      (node (ref "C124") (pin "1") (pinfunction "1_1") (pintype "passive"))
      (node (ref "C125") (pin "1") (pinfunction "1_1") (pintype "passive"))
      (node (ref "C126") (pin "1") (pinfunction "1_1") (pintype "passive"))
      (node (ref "C130") (pin "1") (pinfunction "1_1") (pintype "passive"))
      (node (ref "C131") (pin "2") (pinfunction "2_2") (pintype "passive"))
      (node (ref "C174") (pin "2") (pinfunction "2_2") (pintype "passive"))
      (node (ref "C184") (pin "2") (pinfunction "2_2") (pintype "passive"))
      (node (ref "C185") (pin "2") (pinfunction "2_2") (pintype "passive"))
      (node (ref "C186") (pin "2") (pinfunction "2_2") (pintype "passive"))
      (node (ref "C204") (pin "2") (pinfunction "2_2") (pintype "passive"))
      (node (ref "C205") (pin "2") (pinfunction "2_2") (pintype "passive"))
      (node (ref "C206") (pin "2") (pinfunction "2_2") (pintype "passive"))
      (node (ref "C207") (pin "2") (pinfunction "2_2") (pintype "passive"))
      (node (ref "C208") (pin "2") (pinfunction "2_2") (pintype "passive"))
      (node (ref "C209") (pin "2") (pinfunction "2_2") (pintype "passive"))
      (node (ref "C39") (pin "2") (pinfunction "2_2") (pintype "passive"))
      (node (ref "C40") (pin "2") (pinfunction "2_2") (pintype "passive"))
      (node (ref "C41") (pin "2") (pinfunction "2_2") (pintype "passive"))
      (node (ref "C42") (pin "2") (pinfunction "2_2") (pintype "passive"))
      (node (ref "C47") (pin "1") (pinfunction "1_1") (pintype "passive"))
      (node (ref "C51") (pin "2") (pinfunction "2_2") (pintype "passive"))
      (node (ref "C95") (pin "1") (pinfunction "1_1") (pintype "passive"))
      (node (ref "C96") (pin "2") (pinfunction "2_2") (pintype "passive"))
      (node (ref "C97") (pin "2") (pinfunction "2_2") (pintype "passive"))
      (node (ref "C98") (pin "2") (pinfunction "2_2") (pintype "passive"))
      (node (ref "C99") (pin "2") (pinfunction "2_2") (pintype "passive"))
      (node (ref "R10") (pin "2") (pinfunction "2_2") (pintype "passive"))
      (node (ref "R32") (pin "1") (pinfunction "1_1") (pintype "passive"))
      (node (ref "R33") (pin "1") (pinfunction "1_1") (pintype "passive"))
      (node (ref "U14") (pin "0") (pinfunction "EPAD_0") (pintype "passive"))
      (node (ref "U14") (pin "11") (pinfunction "GND_RF_11") (pintype "passive"))
      (node (ref "U14") (pin "18") (pinfunction "GND_VCO_18") (pintype "passive"))
      (node (ref "U14") (pin "21") (pinfunction "GND_TUNE_21") (pintype "passive"))
      (node (ref "U14") (pin "27") (pinfunction "GND_DIG_27") (pintype "passive"))
      (node (ref "U14") (pin "31") (pinfunction "GND_SD_31") (pintype "passive"))
      (node (ref "U14") (pin "8") (pinfunction "GND_CP_8") (pintype "passive"))
      (node (ref "U14") (pin "9") (pinfunction "GND_PLL_9") (pintype "passive"))
      (node (ref "U15") (pin "0") (pinfunction "PAD_0") (pintype "passive"))
      (node (ref "U15") (pin "5") (pinfunction "GND_5") (pintype "passive"))
      (node (ref "U16") (pin "0") (pinfunction "PAD_0") (pintype "passive"))
      (node (ref "U25") (pin "0") (pinfunction "EPAD_0") (pintype "passive"))
      (node (ref "U25") (pin "1") (pinfunction "GND_1") (pintype "passive"))
      (node (ref "U25") (pin "12") (pinfunction "GND_12") (pintype "passive"))
      (node (ref "U25") (pin "14") (pinfunction "GND_14") (pintype "passive"))
      (node (ref "U25") (pin "17") (pinfunction "GND_17") (pintype "passive"))
      (node (ref "U25") (pin "19") (pinfunction "GND_19") (pintype "passive"))
      (node (ref "U25") (pin "2") (pinfunction "GND_2") (pintype "passive"))
      (node (ref "U25") (pin "23") (pinfunction "GND_23") (pintype "passive"))
      (node (ref "U25") (pin "5") (pinfunction "GND_5") (pintype "passive"))
      (node (ref "U25") (pin "6") (pinfunction "GND_6") (pintype "passive"))
      (node (ref "U25") (pin "8") (pinfunction "GND_8") (pintype "passive"))
      (node (ref "Y3") (pin "1") (pinfunction "GND_1") (pintype "passive"))
      (node (ref "Y3") (pin "3") (pinfunction "GND_3") (pintype "passive"))
      (node (ref "Y3") (pin "4") (pinfunction "GND_4") (pintype "passive"))
      (node (ref "Y3") (pin "6") (pinfunction "GND_6") (pintype "passive"))
      (node (ref "Y4") (pin "1") (pinfunction "GND_1") (pintype "passive"))
      (node (ref "Y4") (pin "3") (pinfunction "GND_3") (pintype "passive"))
      (node (ref "Y4") (pin "4") (pinfunction "GND_4") (pintype "passive"))
      (node (ref "Y4") (pin "6") (pinfunction "GND_6") (pintype "passive"))
      (node (ref "Y5") (pin "1") (pinfunction "GND_1") (pintype "passive"))
      (node (ref "Y5") (pin "3") (pinfunction "GND_3") (pintype "passive"))
      (node (ref "Y5") (pin "4") (pinfunction "GND_4") (pintype "passive"))
      (node (ref "Y5") (pin "6") (pinfunction "GND_6") (pintype "passive"))
      (node (ref "Y6") (pin "1") (pinfunction "GND_1") (pintype "passive"))
      (node (ref "Y6") (pin "3") (pinfunction "GND_3") (pintype "passive"))
      (node (ref "Y6") (pin "4") (pinfunction "GND_4") (pintype "passive"))
      (node (ref "Y6") (pin "6") (pinfunction "GND_6") (pintype "passive"))
    )
    (net (code "23") (name "Net-(Ant4-Pad1)") (class "Default")
      (node (ref "Ant4") (pin "1") (pinfunction "1_1") (pintype "passive"))
      (node (ref "C222") (pin "1") (pinfunction "1_1") (pintype "passive"))
    )
    (net (code "24") (name "Net-(B1-D2)") (class "Default")
      (node (ref "B1") (pin "6") (pinfunction "D2_6") (pintype "passive"))
      (node (ref "C127") (pin "1") (pinfunction "1_1") (pintype "passive"))
      (node (ref "U25") (pin "20") (pinfunction "IFOP_20") (pintype "passive"))
    )
    (net (code "25") (name "Net-(B1-GND{slash}DC-Pad1)") (class "Default")
      (node (ref "B1") (pin "1") (pinfunction "GND/DC_1") (pintype "passive"))
      (node (ref "C116") (pin "2") (pinfunction "2_2") (pintype "passive"))
      (node (ref "R78") (pin "2") (pinfunction "2_2") (pintype "passive"))
      (node (ref "R79") (pin "1") (pinfunction "1_1") (pintype "passive"))
    )
    (net (code "26") (name "Net-(B1-GND{slash}DC-Pad3)") (class "Default")
      (node (ref "B1") (pin "3") (pinfunction "GND/DC_3") (pintype "passive"))
      (node (ref "C117") (pin "2") (pinfunction "2_2") (pintype "passive"))
      (node (ref "R79") (pin "2") (pinfunction "2_2") (pintype "passive"))
    )
    (net (code "27") (name "Net-(B1-SE)") (class "Default")
      (node (ref "B1") (pin "2") (pinfunction "SE_2") (pintype "passive"))
      (node (ref "C111") (pin "2") (pinfunction "2_2") (pintype "passive"))
    )
    (net (code "28") (name "Net-(C100-Pad2)") (class "Default")
      (node (ref "C100") (pin "2") (pinfunction "2_2") (pintype "passive"))
      (node (ref "R31") (pin "2") (pinfunction "2_2") (pintype "passive"))
    )
    (net (code "29") (name "Net-(C102-Pad1)") (class "Default")
      (node (ref "C102") (pin "1") (pinfunction "1_1") (pintype "passive"))
      (node (ref "Y3") (pin "2") (pinfunction "RF_2") (pintype "passive"))
    )
    (net (code "30") (name "Net-(C103-Pad2)") (class "Default")
      (node (ref "C103") (pin "2") (pinfunction "2_2") (pintype "passive"))
      (node (ref "Y4") (pin "5") (pinfunction "RF_5") (pintype "passive"))
    )
    (net (code "31") (name "Net-(C105-Pad1)") (class "Default")
      (node (ref "C105") (pin "1") (pinfunction "1_1") (pintype "passive"))
      (node (ref "Y4") (pin "2") (pinfunction "RF_2") (pintype "passive"))
    )
    (net (code "32") (name "Net-(C105-Pad2)") (class "Default")
      (node (ref "C105") (pin "2") (pinfunction "2_2") (pintype "passive"))
      (node (ref "Y3") (pin "5") (pinfunction "RF_5") (pintype "passive"))
    )
    (net (code "33") (name "Net-(C112-Pad1)") (class "Default")
      (node (ref "C112") (pin "1") (pinfunction "1_1") (pintype "passive"))
      (node (ref "Y5") (pin "2") (pinfunction "RF_2") (pintype "passive"))
    )
    (net (code "34") (name "Net-(C113-Pad2)") (class "Default")
      (node (ref "C113") (pin "2") (pinfunction "2_2") (pintype "passive"))
      (node (ref "Y6") (pin "5") (pinfunction "RF_5") (pintype "passive"))
    )
    (net (code "35") (name "Net-(C114-Pad1)") (class "Default")
      (node (ref "C114") (pin "1") (pinfunction "1_1") (pintype "passive"))
      (node (ref "Y6") (pin "2") (pinfunction "RF_2") (pintype "passive"))
    )
    (net (code "36") (name "Net-(C114-Pad2)") (class "Default")
      (node (ref "C114") (pin "2") (pinfunction "2_2") (pintype "passive"))
      (node (ref "Y5") (pin "5") (pinfunction "RF_5") (pintype "passive"))
    )
    (net (code "37") (name "Net-(C174-Pad1)") (class "Default")
      (node (ref "C174") (pin "1") (pinfunction "1_1") (pintype "passive"))
      (node (ref "C42") (pin "1") (pinfunction "1_1") (pintype "passive"))
      (node (ref "FB7") (pin "2") (pinfunction "2_2") (pintype "passive"))
      (node (ref "L1") (pin "1") (pinfunction "1_1") (pintype "passive"))
      (node (ref "L4") (pin "1") (pinfunction "1_1") (pintype "passive"))
      (node (ref "R28") (pin "1") (pinfunction "1_1") (pintype "passive"))
      (node (ref "R72") (pin "1") (pinfunction "1_1") (pintype "passive"))
    )
    (net (code "38") (name "Net-(U14-BIAS_FILT)") (class "Default")
      (node (ref "C186") (pin "1") (pinfunction "1_1") (pintype "passive"))
      (node (ref "U14") (pin "23") (pinfunction "BIAS_FILT_23") (pintype "passive"))
    )
    (net (code "39") (name "Net-(U14-CP_OUT)") (class "Default")
      (node (ref "C100") (pin "1") (pinfunction "1_1") (pintype "passive"))
      (node (ref "C51") (pin "1") (pinfunction "1_1") (pintype "passive"))
      (node (ref "R73") (pin "2") (pinfunction "2_2") (pintype "passive"))
      (node (ref "U14") (pin "7") (pinfunction "CP_OUT_7") (pintype "passive"))
    )
    (net (code "40") (name "Net-(U14-CS)") (class "Default")
      (node (ref "C204") (pin "1") (pinfunction "1_1") (pintype "passive"))
      (node (ref "R114") (pin "1") (pinfunction "1_1") (pintype "passive"))
      (node (ref "U14") (pin "3") (pinfunction "CS_3") (pintype "passive"))
    )
    (net (code "41") (name "Net-(U14-ENABLE)") (class "Default")
      (node (ref "R30") (pin "1") (pinfunction "1_1") (pintype "passive"))
      (node (ref "U14") (pin "4") (pinfunction "ENABLE_4") (pintype "passive"))
    )
    (net (code "42") (name "Net-(U14-LD)") (class "Default")
      (node (ref "C208") (pin "1") (pinfunction "1_1") (pintype "passive"))
      (node (ref "R116") (pin "1") (pinfunction "1_1") (pintype "passive"))
      (node (ref "U14") (pin "25") (pinfunction "LD_25") (pintype "passive"))
    )
    (net (code "43") (name "Net-(U14-MOSI)") (class "Default")
      (node (ref "C205") (pin "1") (pinfunction "1_1") (pintype "passive"))
      (node (ref "R113") (pin "1") (pinfunction "1_1") (pintype "passive"))
      (node (ref "U14") (pin "2") (pinfunction "MOSI_2") (pintype "passive"))
    )
    (net (code "44") (name "Net-(U14-MUX)") (class "Default")
      (node (ref "C207") (pin "1") (pinfunction "1_1") (pintype "passive"))
      (node (ref "R115") (pin "1") (pinfunction "1_1") (pintype "passive"))
      (node (ref "U14") (pin "30") (pinfunction "MUX_30") (pintype "passive"))
    )
    (net (code "45") (name "Net-(U14-NOISE_FILT)") (class "Default")
      (node (ref "C101") (pin "1") (pinfunction "1_1") (pintype "passive"))
      (node (ref "U14") (pin "19") (pinfunction "NOISE_FILT_19") (pintype "passive"))
    )
    (net (code "46") (name "Net-(U14-REF_IN)") (class "Default")
      (node (ref "C219") (pin "2") (pinfunction "2_2") (pintype "passive"))
      (node (ref "U14") (pin "29") (pinfunction "REF_IN_29") (pintype "passive"))
    )
    (net (code "47") (name "Net-(U14-REG)") (class "Default")
      (node (ref "C185") (pin "1") (pinfunction "1_1") (pintype "passive"))
      (node (ref "U14") (pin "24") (pinfunction "REG_24") (pintype "passive"))
    )
    (net (code "48") (name "Net-(U14-RFB_N)") (class "Default")
      (node (ref "R28") (pin "2") (pinfunction "2_2") (pintype "passive"))
      (node (ref "U14") (pin "15") (pinfunction "RFB_N_15") (pintype "passive"))
    )
    (net (code "49") (name "Net-(U14-RFB_P)") (class "Default")
      (node (ref "R72") (pin "2") (pinfunction "2_2") (pintype "passive"))
      (node (ref "U14") (pin "14") (pinfunction "RFB_P_14") (pintype "passive"))
    )
    (net (code "50") (name "Net-(U14-RFOUT_EN)") (class "Default")
      (node (ref "C209") (pin "1") (pinfunction "1_1") (pintype "passive"))
      (node (ref "R117") (pin "1") (pinfunction "1_1") (pintype "passive"))
      (node (ref "U14") (pin "26") (pinfunction "RFOUT_EN_26") (pintype "passive"))
    )
    (net (code "51") (name "Net-(U14-RSET)") (class "Default")
      (node (ref "R32") (pin "2") (pinfunction "2_2") (pintype "passive"))
      (node (ref "U14") (pin "22") (pinfunction "RSET_22") (pintype "passive"))
    )
    (net (code "52") (name "Net-(U14-SCLK)") (class "Default")
      (node (ref "C206") (pin "1") (pinfunction "1_1") (pintype "passive"))
      (node (ref "R112") (pin "1") (pinfunction "1_1") (pintype "passive"))
      (node (ref "U14") (pin "1") (pinfunction "SCLK_1") (pintype "passive"))
    )
    (net (code "53") (name "Net-(U14-SW)") (class "Default")
      (node (ref "R31") (pin "1") (pinfunction "1_1") (pintype "passive"))
      (node (ref "R33") (pin "2") (pinfunction "2_2") (pintype "passive"))
      (node (ref "U14") (pin "5") (pinfunction "SW_5") (pintype "passive"))
    )
    (net (code "54") (name "Net-(U14-VCC_CP)") (class "Default")
      (node (ref "C39") (pin "1") (pinfunction "1_1") (pintype "passive"))
      (node (ref "C40") (pin "1") (pinfunction "1_1") (pintype "passive"))
      (node (ref "C41") (pin "1") (pinfunction "1_1") (pintype "passive"))
      (node (ref "C98") (pin "1") (pinfunction "1_1") (pintype "passive"))
      (node (ref "FB5") (pin "1") (pinfunction "1_1") (pintype "passive"))
      (node (ref "U14") (pin "10") (pinfunction "VCC_PLL_10") (pintype "passive"))
      (node (ref "U14") (pin "6") (pinfunction "VCC_CP_6") (pintype "passive"))
    )
    (net (code "55") (name "Net-(U14-VCC_DIG)") (class "Default")
      (node (ref "C131") (pin "1") (pinfunction "1_1") (pintype "passive"))
      (node (ref "C99") (pin "1") (pinfunction "1_1") (pintype "passive"))
      (node (ref "FB4") (pin "2") (pinfunction "2_2") (pintype "passive"))
      (node (ref "U14") (pin "28") (pinfunction "VCC_DIG_28") (pintype "passive"))
      (node (ref "U14") (pin "32") (pinfunction "VCC_SD_32") (pintype "passive"))
    )
    (net (code "56") (name "Net-(U14-VCC_RF)") (class "Default")
      (node (ref "C96") (pin "1") (pinfunction "1_1") (pintype "passive"))
      (node (ref "C97") (pin "1") (pinfunction "1_1") (pintype "passive"))
      (node (ref "FB3") (pin "1") (pinfunction "1_1") (pintype "passive"))
      (node (ref "U14") (pin "16") (pinfunction "VCC_RF_16") (pintype "passive"))
      (node (ref "U14") (pin "17") (pinfunction "VCC_VCO_17") (pintype "passive"))
    )
    (net (code "57") (name "Net-(U15-J1)") (class "Default")
      (node (ref "C113") (pin "1") (pinfunction "1_1") (pintype "passive"))
      (node (ref "U15") (pin "6") (pinfunction "J1_6") (pintype "passive"))
    )
    (net (code "58") (name "Net-(U15-J2)") (class "Default")
      (node (ref "C103") (pin "1") (pinfunction "1_1") (pintype "passive"))
      (node (ref "U15") (pin "4") (pinfunction "J2_4") (pintype "passive"))
    )
    (net (code "59") (name "Net-(U15-V1)") (class "Default")
      (node (ref "C107") (pin "2") (pinfunction "2_2") (pintype "passive"))
      (node (ref "R76") (pin "2") (pinfunction "2_2") (pintype "passive"))
      (node (ref "U15") (pin "1") (pinfunction "V1_1") (pintype "passive"))
    )
    (net (code "60") (name "Net-(U15-V2)") (class "Default")
      (node (ref "C104") (pin "2") (pinfunction "2_2") (pintype "passive"))
      (node (ref "R74") (pin "2") (pinfunction "2_2") (pintype "passive"))
      (node (ref "U15") (pin "3") (pinfunction "V2_3") (pintype "passive"))
    )
    (net (code "61") (name "Net-(U16-J1)") (class "Default")
      (node (ref "C102") (pin "2") (pinfunction "2_2") (pintype "passive"))
      (node (ref "U16") (pin "6") (pinfunction "J1_6") (pintype "passive"))
    )
    (net (code "62") (name "Net-(U16-J2)") (class "Default")
      (node (ref "C112") (pin "2") (pinfunction "2_2") (pintype "passive"))
      (node (ref "U16") (pin "4") (pinfunction "J2_4") (pintype "passive"))
    )
    (net (code "63") (name "Net-(U16-V1)") (class "Default")
      (node (ref "C106") (pin "2") (pinfunction "2_2") (pintype "passive"))
      (node (ref "R75") (pin "2") (pinfunction "2_2") (pintype "passive"))
      (node (ref "U16") (pin "1") (pinfunction "V1_1") (pintype "passive"))
    )
    (net (code "64") (name "Net-(U16-V2)") (class "Default")
      (node (ref "C115") (pin "2") (pinfunction "2_2") (pintype "passive"))
      (node (ref "R77") (pin "2") (pinfunction "2_2") (pintype "passive"))
      (node (ref "U16") (pin "3") (pinfunction "V2_3") (pintype "passive"))
    )
    (net (code "65") (name "Net-(U17-A+)") (class "Default")
      (node (ref "C175") (pin "1") (pinfunction "1_1") (pintype "passive"))
      (node (ref "U17") (pin "1") (pinfunction "A+_1") (pintype "passive"))
    )
    (net (code "66") (name "Net-(U17-A-)") (class "Default")
      (node (ref "C128") (pin "1") (pinfunction "1_1") (pintype "passive"))
      (node (ref "U17") (pin "3") (pinfunction "A-_3") (pintype "passive"))
    )
    (net (code "67") (name "Net-(U17-B+)") (class "Default")
      (node (ref "C129") (pin "1") (pinfunction "1_1") (pintype "passive"))
      (node (ref "U17") (pin "5") (pinfunction "B+_5") (pintype "passive"))
    )
    (net (code "68") (name "Net-(U17-B-)") (class "Default")
      (node (ref "C47") (pin "2") (pinfunction "2_2") (pintype "passive"))
      (node (ref "U17") (pin "4") (pinfunction "B-_4") (pintype "passive"))
    )
    (net (code "69") (name "Net-(U25-ENBL)") (class "Default")
      (node (ref "R10") (pin "1") (pinfunction "1_1") (pintype "passive"))
      (node (ref "U25") (pin "9") (pinfunction "ENBL_9") (pintype "passive"))
    )
    (net (code "70") (name "Net-(U25-LON)") (class "Default")
      (node (ref "C133") (pin "2") (pinfunction "2_2") (pintype "passive"))
      (node (ref "U25") (pin "4") (pinfunction "LON_4") (pintype "passive"))
    )
    (net (code "71") (name "Net-(U25-LOP)") (class "Default")
      (node (ref "C134") (pin "2") (pinfunction "2_2") (pintype "passive"))
      (node (ref "U25") (pin "3") (pinfunction "LOP_3") (pintype "passive"))
    )
    (net (code "72") (name "Net-(U25-RFIN)") (class "Default")
      (node (ref "C128") (pin "2") (pinfunction "2_2") (pintype "passive"))
      (node (ref "U25") (pin "16") (pinfunction "RFIN_16") (pintype "passive"))
    )
    (net (code "73") (name "Net-(U25-RFIP)") (class "Default")
      (node (ref "C175") (pin "2") (pinfunction "2_2") (pintype "passive"))
      (node (ref "U25") (pin "15") (pinfunction "RFIP_15") (pintype "passive"))
    )
    (net (code "74") (name "unconnected-(B1-NC-Pad5)") (class "Default")
      (node (ref "B1") (pin "5") (pinfunction "NC_5") (pintype "passive+no_connect"))
    )
    (net (code "75") (name "unconnected-(U16-GND-Pad5)") (class "Default")
      (node (ref "U16") (pin "5") (pinfunction "GND_5") (pintype "passive"))
    )
    (net (code "76") (name "unconnected-(U17-C-Pad2)") (class "Default")
      (node (ref "U17") (pin "2") (pinfunction "C_2") (pintype "passive"))
    )
    (net (code "77") (name "unconnected-(U25-NC-Pad22)") (class "Default")
      (node (ref "U25") (pin "22") (pinfunction "NC_22") (pintype "passive"))
    )
  )
)
